# GSM_UNIT.net
KiCad netlist of a schematic drawn in Altium Designer
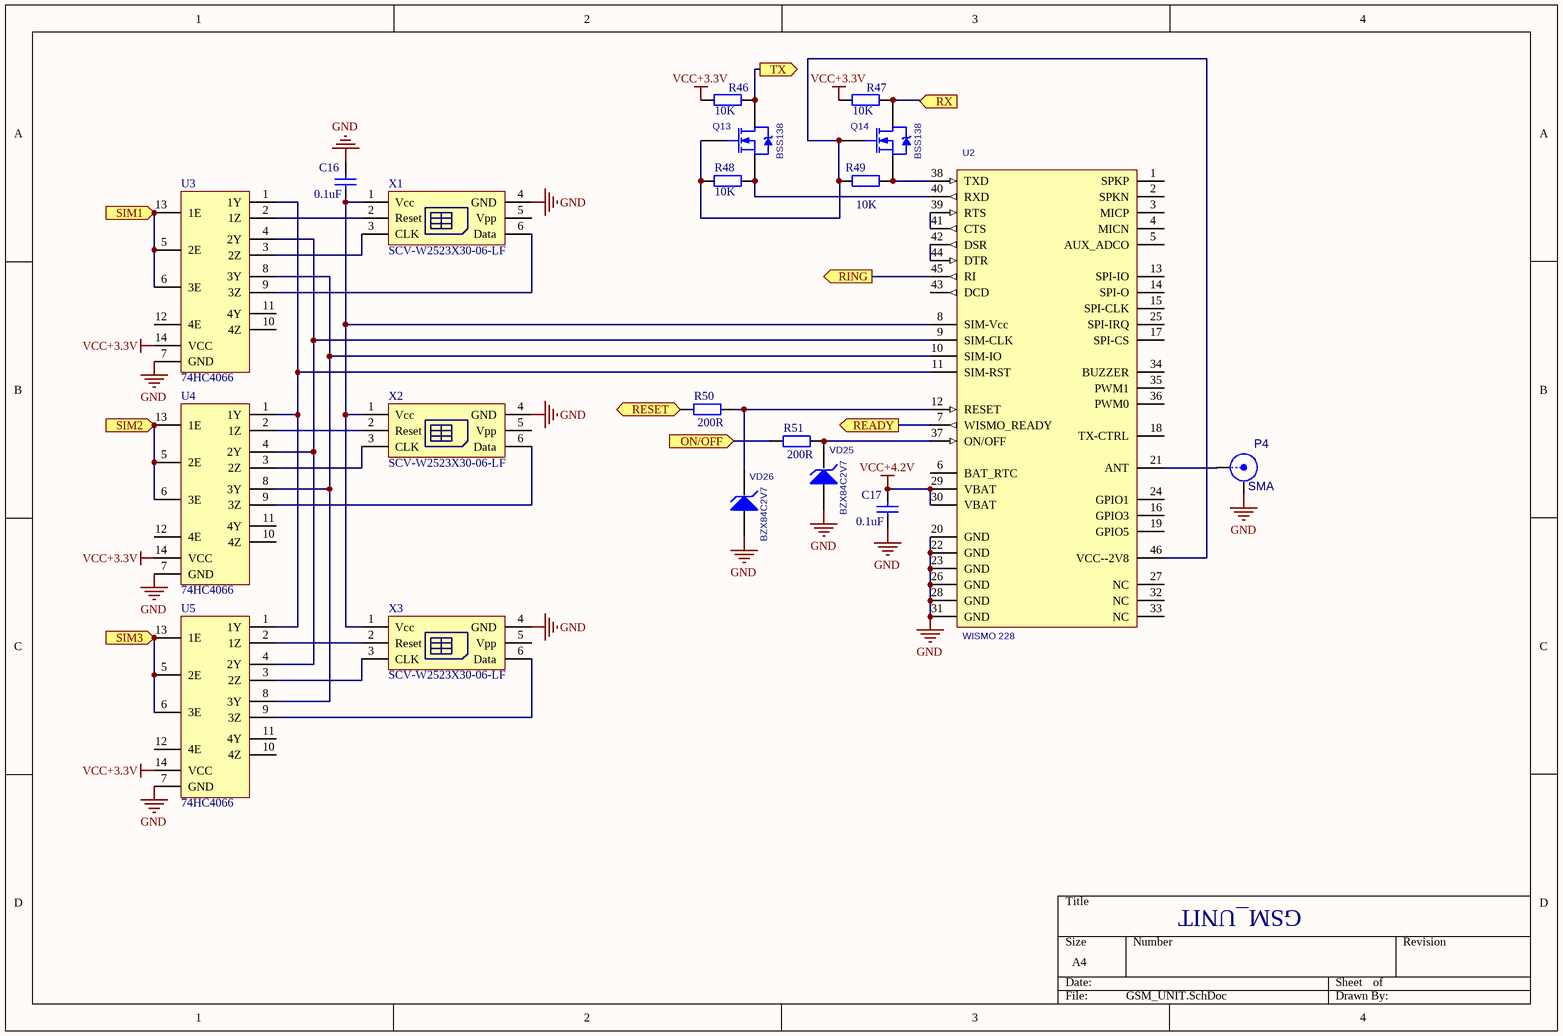
[diagram p0: GSM_UNIT.SchDoc]

(export (version "E")
  (design (tool "Eeschema 10.0.6"))
  (components
    (comp (ref "C16")
      (value "0.1uF")
      (footprint "C0603")
      (description "Capasitor_SMD_0808/")
      (fields (field (name "Comment") "0805"))
      (libsource (lib "NEW") (part "Capasitor_SMD_0805"))
    )
    (comp (ref "C17")
      (value "0.1uF")
      (footprint "C0603")
      (description "Capasitor_SMD_0808/")
      (fields (field (name "Comment") "0805"))
      (libsource (lib "NEW") (part "Capasitor_SMD_0805"))
    )
    (comp (ref "P4")
      (value "SMA")
      (footprint "SMA")
      (fields (field (name "PUBLISHER") "Altium Limited"))
      (libsource (lib "NEW") (part "SMA"))
    )
    (comp (ref "Q13")
      (value "BSS138")
      (footprint "SOT23")
      (description "BSS138-SOT23")
      (libsource (lib "NEW") (part "BSS138-SOT23"))
    )
    (comp (ref "Q14")
      (value "BSS138")
      (footprint "SOT23")
      (description "BSS138-SOT23")
      (libsource (lib "NEW") (part "BSS138-SOT23"))
    )
    (comp (ref "R46")
      (value "10K")
      (footprint "C0603")
      (description "Resistor")
      (fields (field (name "Comment") "RES"))
      (libsource (lib "NEW") (part "RES"))
    )
    (comp (ref "R47")
      (value "10K")
      (footprint "C0603")
      (description "Resistor")
      (fields (field (name "Comment") "RES"))
      (libsource (lib "NEW") (part "RES"))
    )
    (comp (ref "R48")
      (value "10K")
      (footprint "C0603")
      (description "Resistor")
      (fields (field (name "Comment") "RES"))
      (libsource (lib "NEW") (part "RES"))
    )
    (comp (ref "R49")
      (value "10K")
      (footprint "C0603")
      (description "Resistor")
      (fields (field (name "Comment") "RES"))
      (libsource (lib "NEW") (part "RES"))
    )
    (comp (ref "R50")
      (value "200R")
      (footprint "C0603")
      (description "Resistor")
      (fields (field (name "Comment") "RES"))
      (libsource (lib "NEW") (part "RES"))
    )
    (comp (ref "R51")
      (value "200R")
      (footprint "C0603")
      (description "Resistor")
      (fields (field (name "Comment") "RES"))
      (libsource (lib "NEW") (part "RES"))
    )
    (comp (ref "U2") (value "WISMO 228") (footprint "WISMO") (libsource (lib "NEW") (part "WISMO 228")))
    (comp (ref "U3") (value "74HC4066") (footprint "SO-14") (libsource (lib "NEW") (part "74HC4066")))
    (comp (ref "U4") (value "74HC4066") (footprint "SO-14") (libsource (lib "NEW") (part "74HC4066")))
    (comp (ref "U5") (value "74HC4066") (footprint "SO-14") (libsource (lib "NEW") (part "74HC4066")))
    (comp (ref "VD25")
      (value "BZX84C2V7")
      (footprint "SOT23")
      (description "BZX84C")
      (libsource (lib "NEW") (part "BZX84C"))
    )
    (comp (ref "VD26")
      (value "BZX84C2V7")
      (footprint "SOT23")
      (description "BZX84C")
      (libsource (lib "NEW") (part "BZX84C"))
    )
    (comp (ref "X1")
      (value "SCV-W2523X30-06-LF")
      (footprint "SCV-W2523X30-06-LF")
      (description "SIM Cartreader")
      (libsource (lib "NEW") (part "SCV-W2523X30-06-LF"))
    )
    (comp (ref "X2")
      (value "SCV-W2523X30-06-LF")
      (footprint "SCV-W2523X30-06-LF")
      (description "SIM Cartreader")
      (libsource (lib "NEW") (part "SCV-W2523X30-06-LF"))
    )
    (comp (ref "X3")
      (value "SCV-W2523X30-06-LF")
      (footprint "SCV-W2523X30-06-LF")
      (description "SIM Cartreader")
      (libsource (lib "NEW") (part "SCV-W2523X30-06-LF"))
    )
  )
  (nets
    (net (code "1") (name "/ON{slash}OFF") (class "Default")
      (node (ref "R51") (pin "1") (pinfunction "1_1") (pintype "passive"))
    )
    (net (code "2") (name "/READY") (class "Default")
      (node (ref "U2") (pin "7") (pinfunction "WISMO_READY_7") (pintype "output"))
    )
    (net (code "3") (name "/RESET") (class "Default")
      (node (ref "R50") (pin "1") (pinfunction "1_1") (pintype "passive"))
    )
    (net (code "4") (name "/RING") (class "Default")
      (node (ref "U2") (pin "45") (pinfunction "RI_45") (pintype "output"))
    )
    (net (code "5") (name "/RX") (class "Default")
      (node (ref "Q14") (pin "3") (pinfunction "D_3") (pintype "passive"))
      (node (ref "R47") (pin "2") (pinfunction "2_2") (pintype "passive"))
    )
    (net (code "6") (name "/SIM1") (class "Default")
      (node (ref "U3") (pin "13") (pinfunction "1E_13") (pintype "passive"))
      (node (ref "U3") (pin "5") (pinfunction "2E_5") (pintype "passive"))
      (node (ref "U3") (pin "6") (pinfunction "3E_6") (pintype "passive"))
    )
    (net (code "7") (name "/SIM2") (class "Default")
      (node (ref "U4") (pin "13") (pinfunction "1E_13") (pintype "passive"))
      (node (ref "U4") (pin "5") (pinfunction "2E_5") (pintype "passive"))
      (node (ref "U4") (pin "6") (pinfunction "3E_6") (pintype "passive"))
    )
    (net (code "8") (name "/SIM3") (class "Default")
      (node (ref "U5") (pin "13") (pinfunction "1E_13") (pintype "passive"))
      (node (ref "U5") (pin "5") (pinfunction "2E_5") (pintype "passive"))
      (node (ref "U5") (pin "6") (pinfunction "3E_6") (pintype "passive"))
    )
    (net (code "9") (name "/TX") (class "Default")
      (node (ref "Q13") (pin "3") (pinfunction "D_3") (pintype "passive"))
      (node (ref "R46") (pin "2") (pinfunction "2_2") (pintype "passive"))
    )
    (net (code "10") (name "GND") (class "Default")
      (node (ref "C16") (pin "1") (pinfunction "1_1") (pintype "passive"))
      (node (ref "C17") (pin "2") (pinfunction "2_2") (pintype "passive"))
      (node (ref "P4") (pin "2") (pinfunction "Y_2") (pintype "passive"))
      (node (ref "U2") (pin "20") (pinfunction "GND_20") (pintype "passive"))
      (node (ref "U2") (pin "22") (pinfunction "GND_22") (pintype "passive"))
      (node (ref "U2") (pin "23") (pinfunction "GND_23") (pintype "passive"))
      (node (ref "U2") (pin "26") (pinfunction "GND_26") (pintype "passive"))
      (node (ref "U2") (pin "28") (pinfunction "GND_28") (pintype "passive"))
      (node (ref "U2") (pin "31") (pinfunction "GND_31") (pintype "passive"))
      (node (ref "U3") (pin "7") (pinfunction "GND_7") (pintype "passive"))
      (node (ref "U4") (pin "7") (pinfunction "GND_7") (pintype "passive"))
      (node (ref "U5") (pin "7") (pinfunction "GND_7") (pintype "passive"))
      (node (ref "VD25") (pin "1") (pinfunction "A_1") (pintype "passive"))
      (node (ref "VD26") (pin "1") (pinfunction "A_1") (pintype "passive"))
      (node (ref "X1") (pin "4") (pinfunction "GND_4") (pintype "passive"))
      (node (ref "X2") (pin "4") (pinfunction "GND_4") (pintype "passive"))
      (node (ref "X3") (pin "4") (pinfunction "GND_4") (pintype "passive"))
    )
    (net (code "11") (name "Net-(P4-X)") (class "Default")
      (node (ref "P4") (pin "1") (pinfunction "X_1") (pintype "passive"))
      (node (ref "U2") (pin "21") (pinfunction "ANT_21") (pintype "passive"))
    )
    (net (code "12") (name "Net-(Q13-G)") (class "Default")
      (node (ref "Q13") (pin "1") (pinfunction "G_1") (pintype "passive"))
      (node (ref "Q14") (pin "1") (pinfunction "G_1") (pintype "passive"))
      (node (ref "R48") (pin "1") (pinfunction "1_1") (pintype "passive"))
      (node (ref "R49") (pin "1") (pinfunction "1_1") (pintype "passive"))
      (node (ref "U2") (pin "46") (pinfunction "VCC--2V8_46") (pintype "passive"))
    )
    (net (code "13") (name "Net-(Q13-S)") (class "Default")
      (node (ref "Q13") (pin "2") (pinfunction "S_2") (pintype "passive"))
      (node (ref "R48") (pin "2") (pinfunction "2_2") (pintype "passive"))
      (node (ref "U2") (pin "40") (pinfunction "RXD_40") (pintype "output"))
    )
    (net (code "14") (name "Net-(Q14-S)") (class "Default")
      (node (ref "Q14") (pin "2") (pinfunction "S_2") (pintype "passive"))
      (node (ref "R49") (pin "2") (pinfunction "2_2") (pintype "passive"))
      (node (ref "U2") (pin "38") (pinfunction "TXD_38") (pintype "input"))
    )
    (net (code "15") (name "Net-(U2-CTS)") (class "Default")
      (node (ref "U2") (pin "39") (pinfunction "RTS_39") (pintype "input"))
      (node (ref "U2") (pin "41") (pinfunction "CTS_41") (pintype "output"))
    )
    (net (code "16") (name "Net-(U2-DSR)") (class "Default")
      (node (ref "U2") (pin "42") (pinfunction "DSR_42") (pintype "output"))
      (node (ref "U2") (pin "44") (pinfunction "DTR_44") (pintype "input"))
    )
    (net (code "17") (name "Net-(U2-ON{slash}OFF)") (class "Default")
      (node (ref "R51") (pin "2") (pinfunction "2_2") (pintype "passive"))
      (node (ref "U2") (pin "37") (pinfunction "ON/OFF_37") (pintype "input"))
      (node (ref "VD25") (pin "3") (pinfunction "K_3") (pintype "passive"))
    )
    (net (code "18") (name "Net-(U2-RESET)") (class "Default")
      (node (ref "R50") (pin "2") (pinfunction "2_2") (pintype "passive"))
      (node (ref "U2") (pin "12") (pinfunction "RESET_12") (pintype "input"))
      (node (ref "VD26") (pin "3") (pinfunction "K_3") (pintype "passive"))
    )
    (net (code "19") (name "Net-(U2-SIM-CLK)") (class "Default")
      (node (ref "U2") (pin "9") (pinfunction "SIM-CLK_9") (pintype "passive"))
      (node (ref "U3") (pin "4") (pinfunction "2Y_4") (pintype "passive"))
      (node (ref "U4") (pin "4") (pinfunction "2Y_4") (pintype "passive"))
      (node (ref "U5") (pin "4") (pinfunction "2Y_4") (pintype "passive"))
    )
    (net (code "20") (name "Net-(U2-SIM-IO)") (class "Default")
      (node (ref "U2") (pin "10") (pinfunction "SIM-IO_10") (pintype "passive"))
      (node (ref "U3") (pin "8") (pinfunction "3Y_8") (pintype "passive"))
      (node (ref "U4") (pin "8") (pinfunction "3Y_8") (pintype "passive"))
      (node (ref "U5") (pin "8") (pinfunction "3Y_8") (pintype "passive"))
    )
    (net (code "21") (name "Net-(U2-SIM-RST)") (class "Default")
      (node (ref "U2") (pin "11") (pinfunction "SIM-RST_11") (pintype "passive"))
      (node (ref "U3") (pin "1") (pinfunction "1Y_1") (pintype "passive"))
      (node (ref "U4") (pin "1") (pinfunction "1Y_1") (pintype "passive"))
      (node (ref "U5") (pin "1") (pinfunction "1Y_1") (pintype "passive"))
    )
    (net (code "22") (name "Net-(U2-SIM-Vcc)") (class "Default")
      (node (ref "C16") (pin "2") (pinfunction "2_2") (pintype "passive"))
      (node (ref "U2") (pin "8") (pinfunction "SIM-Vcc_8") (pintype "passive"))
      (node (ref "X1") (pin "1") (pinfunction "Vcc_1") (pintype "passive"))
      (node (ref "X2") (pin "1") (pinfunction "Vcc_1") (pintype "passive"))
      (node (ref "X3") (pin "1") (pinfunction "Vcc_1") (pintype "passive"))
    )
    (net (code "23") (name "Net-(U3-1Z)") (class "Default")
      (node (ref "U3") (pin "2") (pinfunction "1Z_2") (pintype "passive"))
      (node (ref "X1") (pin "2") (pinfunction "Reset_2") (pintype "passive"))
    )
    (net (code "24") (name "Net-(U3-2Z)") (class "Default")
      (node (ref "U3") (pin "3") (pinfunction "2Z_3") (pintype "passive"))
      (node (ref "X1") (pin "3") (pinfunction "CLK_3") (pintype "passive"))
    )
    (net (code "25") (name "Net-(U3-3Z)") (class "Default")
      (node (ref "U3") (pin "9") (pinfunction "3Z_9") (pintype "passive"))
      (node (ref "X1") (pin "6") (pinfunction "Data_6") (pintype "passive"))
    )
    (net (code "26") (name "Net-(U4-1Z)") (class "Default")
      (node (ref "U4") (pin "2") (pinfunction "1Z_2") (pintype "passive"))
      (node (ref "X2") (pin "2") (pinfunction "Reset_2") (pintype "passive"))
    )
    (net (code "27") (name "Net-(U4-2Z)") (class "Default")
      (node (ref "U4") (pin "3") (pinfunction "2Z_3") (pintype "passive"))
      (node (ref "X2") (pin "3") (pinfunction "CLK_3") (pintype "passive"))
    )
    (net (code "28") (name "Net-(U4-3Z)") (class "Default")
      (node (ref "U4") (pin "9") (pinfunction "3Z_9") (pintype "passive"))
      (node (ref "X2") (pin "6") (pinfunction "Data_6") (pintype "passive"))
    )
    (net (code "29") (name "Net-(U5-1Z)") (class "Default")
      (node (ref "U5") (pin "2") (pinfunction "1Z_2") (pintype "passive"))
      (node (ref "X3") (pin "2") (pinfunction "Reset_2") (pintype "passive"))
    )
    (net (code "30") (name "Net-(U5-2Z)") (class "Default")
      (node (ref "U5") (pin "3") (pinfunction "2Z_3") (pintype "passive"))
      (node (ref "X3") (pin "3") (pinfunction "CLK_3") (pintype "passive"))
    )
    (net (code "31") (name "Net-(U5-3Z)") (class "Default")
      (node (ref "U5") (pin "9") (pinfunction "3Z_9") (pintype "passive"))
      (node (ref "X3") (pin "6") (pinfunction "Data_6") (pintype "passive"))
    )
    (net (code "32") (name "VCC+3.3V") (class "Default")
      (node (ref "R46") (pin "1") (pinfunction "1_1") (pintype "passive"))
      (node (ref "R47") (pin "1") (pinfunction "1_1") (pintype "passive"))
      (node (ref "U3") (pin "14") (pinfunction "VCC_14") (pintype "passive"))
      (node (ref "U4") (pin "14") (pinfunction "VCC_14") (pintype "passive"))
      (node (ref "U5") (pin "14") (pinfunction "VCC_14") (pintype "passive"))
    )
    (net (code "33") (name "VCC+4.2V") (class "Default")
      (node (ref "C17") (pin "1") (pinfunction "1_1") (pintype "passive"))
      (node (ref "U2") (pin "29") (pinfunction "VBAT_29") (pintype "passive"))
      (node (ref "U2") (pin "30") (pinfunction "VBAT_30") (pintype "passive"))
    )
    (net (code "34") (name "unconnected-(U2-AUX_ADCO-Pad5)") (class "Default")
      (node (ref "U2") (pin "5") (pinfunction "AUX_ADCO_5") (pintype "passive"))
    )
    (net (code "35") (name "unconnected-(U2-BAT_RTC-Pad6)") (class "Default")
      (node (ref "U2") (pin "6") (pinfunction "BAT_RTC_6") (pintype "passive"))
    )
    (net (code "36") (name "unconnected-(U2-BUZZER-Pad34)") (class "Default")
      (node (ref "U2") (pin "34") (pinfunction "BUZZER_34") (pintype "passive"))
    )
    (net (code "37") (name "unconnected-(U2-DCD-Pad43)") (class "Default")
      (node (ref "U2") (pin "43") (pinfunction "DCD_43") (pintype "output"))
    )
    (net (code "38") (name "unconnected-(U2-GPIO1-Pad24)") (class "Default")
      (node (ref "U2") (pin "24") (pinfunction "GPIO1_24") (pintype "passive"))
    )
    (net (code "39") (name "unconnected-(U2-GPIO3-Pad16)") (class "Default")
      (node (ref "U2") (pin "16") (pinfunction "GPIO3_16") (pintype "passive"))
    )
    (net (code "40") (name "unconnected-(U2-GPIO5-Pad19)") (class "Default")
      (node (ref "U2") (pin "19") (pinfunction "GPIO5_19") (pintype "passive"))
    )
    (net (code "41") (name "unconnected-(U2-MICN-Pad4)") (class "Default")
      (node (ref "U2") (pin "4") (pinfunction "MICN_4") (pintype "passive"))
    )
    (net (code "42") (name "unconnected-(U2-MICP-Pad3)") (class "Default")
      (node (ref "U2") (pin "3") (pinfunction "MICP_3") (pintype "passive"))
    )
    (net (code "43") (name "unconnected-(U2-NC-Pad27)") (class "Default")
      (node (ref "U2") (pin "27") (pinfunction "NC_27") (pintype "passive"))
    )
    (net (code "44") (name "unconnected-(U2-NC-Pad32)") (class "Default")
      (node (ref "U2") (pin "32") (pinfunction "NC_32") (pintype "passive"))
    )
    (net (code "45") (name "unconnected-(U2-NC-Pad33)") (class "Default")
      (node (ref "U2") (pin "33") (pinfunction "NC_33") (pintype "passive"))
    )
    (net (code "46") (name "unconnected-(U2-PWM0-Pad36)") (class "Default")
      (node (ref "U2") (pin "36") (pinfunction "PWM0_36") (pintype "passive"))
    )
    (net (code "47") (name "unconnected-(U2-PWM1-Pad35)") (class "Default")
      (node (ref "U2") (pin "35") (pinfunction "PWM1_35") (pintype "passive"))
    )
    (net (code "48") (name "unconnected-(U2-SPI-CLK-Pad15)") (class "Default")
      (node (ref "U2") (pin "15") (pinfunction "SPI-CLK_15") (pintype "passive"))
    )
    (net (code "49") (name "unconnected-(U2-SPI-CS-Pad17)") (class "Default")
      (node (ref "U2") (pin "17") (pinfunction "SPI-CS_17") (pintype "passive"))
    )
    (net (code "50") (name "unconnected-(U2-SPI-IO-Pad13)") (class "Default")
      (node (ref "U2") (pin "13") (pinfunction "SPI-IO_13") (pintype "passive"))
    )
    (net (code "51") (name "unconnected-(U2-SPI-IRQ-Pad25)") (class "Default")
      (node (ref "U2") (pin "25") (pinfunction "SPI-IRQ_25") (pintype "passive"))
    )
    (net (code "52") (name "unconnected-(U2-SPI-O-Pad14)") (class "Default")
      (node (ref "U2") (pin "14") (pinfunction "SPI-O_14") (pintype "passive"))
    )
    (net (code "53") (name "unconnected-(U2-SPKN-Pad2)") (class "Default")
      (node (ref "U2") (pin "2") (pinfunction "SPKN_2") (pintype "passive"))
    )
    (net (code "54") (name "unconnected-(U2-SPKP-Pad1)") (class "Default")
      (node (ref "U2") (pin "1") (pinfunction "SPKP_1") (pintype "passive"))
    )
    (net (code "55") (name "unconnected-(U2-TX-CTRL-Pad18)") (class "Default")
      (node (ref "U2") (pin "18") (pinfunction "TX-CTRL_18") (pintype "passive"))
    )
    (net (code "56") (name "unconnected-(U3-4E-Pad12)") (class "Default")
      (node (ref "U3") (pin "12") (pinfunction "4E_12") (pintype "passive"))
    )
    (net (code "57") (name "unconnected-(U3-4Y-Pad11)") (class "Default")
      (node (ref "U3") (pin "11") (pinfunction "4Y_11") (pintype "passive"))
    )
    (net (code "58") (name "unconnected-(U3-4Z-Pad10)") (class "Default")
      (node (ref "U3") (pin "10") (pinfunction "4Z_10") (pintype "passive"))
    )
    (net (code "59") (name "unconnected-(U4-4E-Pad12)") (class "Default")
      (node (ref "U4") (pin "12") (pinfunction "4E_12") (pintype "passive"))
    )
    (net (code "60") (name "unconnected-(U4-4Y-Pad11)") (class "Default")
      (node (ref "U4") (pin "11") (pinfunction "4Y_11") (pintype "passive"))
    )
    (net (code "61") (name "unconnected-(U4-4Z-Pad10)") (class "Default")
      (node (ref "U4") (pin "10") (pinfunction "4Z_10") (pintype "passive"))
    )
    (net (code "62") (name "unconnected-(U5-4E-Pad12)") (class "Default")
      (node (ref "U5") (pin "12") (pinfunction "4E_12") (pintype "passive"))
    )
    (net (code "63") (name "unconnected-(U5-4Y-Pad11)") (class "Default")
      (node (ref "U5") (pin "11") (pinfunction "4Y_11") (pintype "passive"))
    )
    (net (code "64") (name "unconnected-(U5-4Z-Pad10)") (class "Default")
      (node (ref "U5") (pin "10") (pinfunction "4Z_10") (pintype "passive"))
    )
    (net (code "65") (name "unconnected-(VD25-Pad2)") (class "Default")
      (node (ref "VD25") (pin "2") (pintype "passive"))
    )
    (net (code "66") (name "unconnected-(VD26-Pad2)") (class "Default")
      (node (ref "VD26") (pin "2") (pintype "passive"))
    )
    (net (code "67") (name "unconnected-(X1-Vpp-Pad5)") (class "Default")
      (node (ref "X1") (pin "5") (pinfunction "Vpp_5") (pintype "passive"))
    )
    (net (code "68") (name "unconnected-(X2-Vpp-Pad5)") (class "Default")
      (node (ref "X2") (pin "5") (pinfunction "Vpp_5") (pintype "passive"))
    )
    (net (code "69") (name "unconnected-(X3-Vpp-Pad5)") (class "Default")
      (node (ref "X3") (pin "5") (pinfunction "Vpp_5") (pintype "passive"))
    )
  )
)
